# schematic.net
KiCad netlist of a schematic drawn in EAGLE
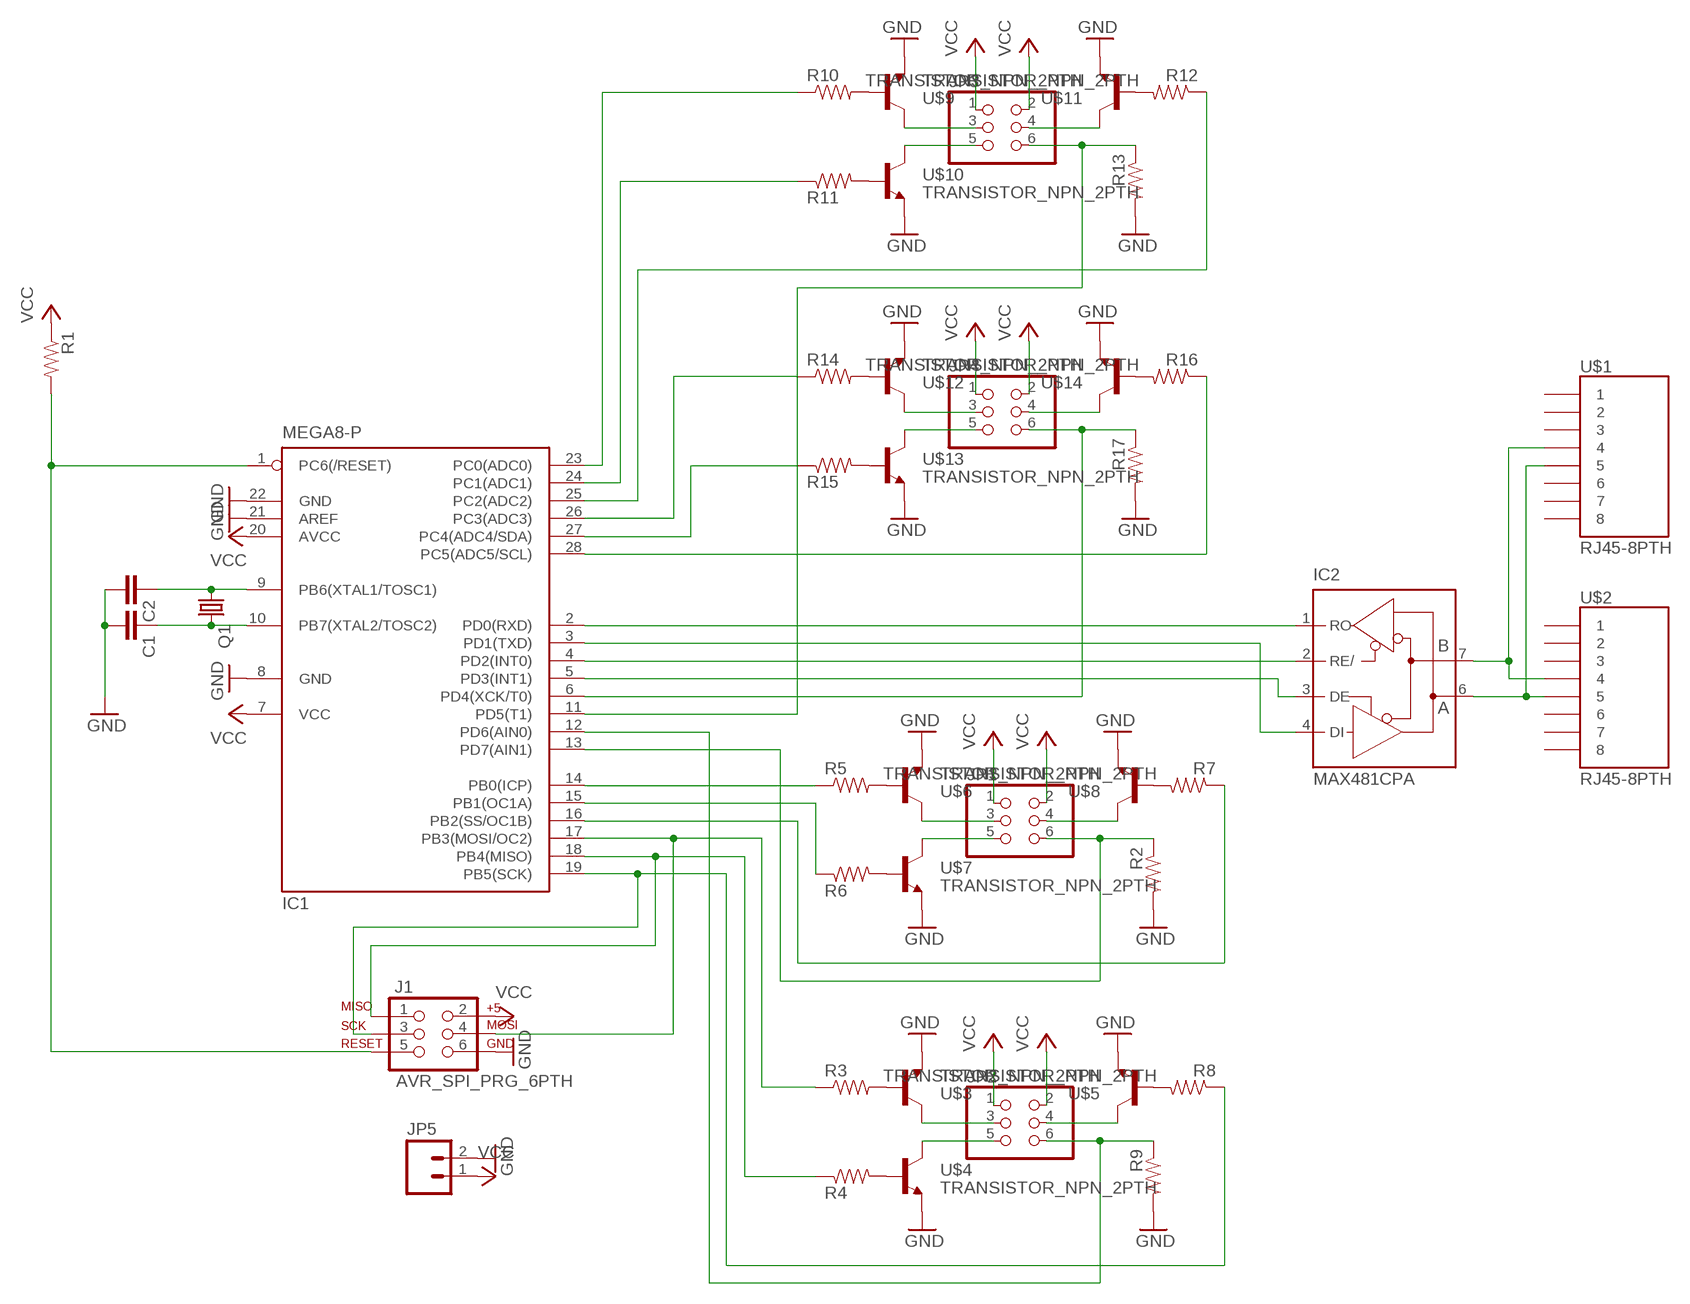
[diagram p0: schematic, sheet 1]

(export (version "E")
  (design (tool "Eeschema 10.0.6"))
  (components
    (comp (ref "C1")
      (value "CAPKIT")
      (footprint "eagle-import:CAP-PTH-SMALL-KIT")
      (libsource (lib "eagle-import") (part "CAPKIT"))
    )
    (comp (ref "C2")
      (value "CAPKIT")
      (footprint "eagle-import:CAP-PTH-SMALL-KIT")
      (libsource (lib "eagle-import") (part "CAPKIT"))
    )
    (comp (ref "IC1")
      (value "MEGA8-P")
      (footprint "eagle-import:DIL28-3")
      (libsource (lib "eagle-import") (part "MEGA8-P"))
    )
    (comp (ref "IC2")
      (value "MAX481CPA")
      (footprint "eagle-import:DIL08")
      (fields (field (name "MPN") "MAX481CPA+"))
      (libsource (lib "eagle-import") (part "MAX481CPA"))
    )
    (comp (ref "J1")
      (value "AVR_SPI_PRG_6PTH")
      (footprint "eagle-import:2X3")
      (libsource (lib "eagle-import") (part "AVR_SPI_PRG_6PTH"))
    )
    (comp (ref "JP1")
      (value "PINHD-2X3")
      (footprint "eagle-import:2X03")
      (libsource (lib "eagle-import") (part "PINHD-2X3"))
    )
    (comp (ref "JP2")
      (value "PINHD-2X3")
      (footprint "eagle-import:2X03")
      (libsource (lib "eagle-import") (part "PINHD-2X3"))
    )
    (comp (ref "JP3")
      (value "PINHD-2X3")
      (footprint "eagle-import:2X03")
      (libsource (lib "eagle-import") (part "PINHD-2X3"))
    )
    (comp (ref "JP4")
      (value "PINHD-2X3")
      (footprint "eagle-import:2X03")
      (libsource (lib "eagle-import") (part "PINHD-2X3"))
    )
    (comp (ref "JP5")
      (value "M023.5MM")
      (footprint "eagle-import:SCREWTERMINAL-3.5MM-2")
      (libsource (lib "eagle-import") (part "M023.5MM"))
    )
    (comp (ref "Q1")
      (value "CRYSTALHC49U-V")
      (footprint "eagle-import:HC49U-V")
      (libsource (lib "eagle-import") (part "CRYSTALHC49U-V"))
    )
    (comp (ref "R1")
      (value "RESISTORPTH-1/4W")
      (footprint "eagle-import:AXIAL-0.4")
      (libsource (lib "eagle-import") (part "RESISTORPTH-1/4W"))
    )
    (comp (ref "R2")
      (value "RESISTORPTH-1/4W")
      (footprint "eagle-import:AXIAL-0.4")
      (libsource (lib "eagle-import") (part "RESISTORPTH-1/4W"))
    )
    (comp (ref "R3")
      (value "RESISTORPTH-1/4W")
      (footprint "eagle-import:AXIAL-0.4")
      (libsource (lib "eagle-import") (part "RESISTORPTH-1/4W"))
    )
    (comp (ref "R4")
      (value "RESISTORPTH-1/4W")
      (footprint "eagle-import:AXIAL-0.4")
      (libsource (lib "eagle-import") (part "RESISTORPTH-1/4W"))
    )
    (comp (ref "R5")
      (value "RESISTORPTH-1/4W")
      (footprint "eagle-import:AXIAL-0.4")
      (libsource (lib "eagle-import") (part "RESISTORPTH-1/4W"))
    )
    (comp (ref "R6")
      (value "RESISTORPTH-1/4W")
      (footprint "eagle-import:AXIAL-0.4")
      (libsource (lib "eagle-import") (part "RESISTORPTH-1/4W"))
    )
    (comp (ref "R7")
      (value "RESISTORPTH-1/4W")
      (footprint "eagle-import:AXIAL-0.4")
      (libsource (lib "eagle-import") (part "RESISTORPTH-1/4W"))
    )
    (comp (ref "R8")
      (value "RESISTORPTH-1/4W")
      (footprint "eagle-import:AXIAL-0.4")
      (libsource (lib "eagle-import") (part "RESISTORPTH-1/4W"))
    )
    (comp (ref "R9")
      (value "RESISTORPTH-1/4W")
      (footprint "eagle-import:AXIAL-0.4")
      (libsource (lib "eagle-import") (part "RESISTORPTH-1/4W"))
    )
    (comp (ref "R10")
      (value "RESISTORPTH-1/4W")
      (footprint "eagle-import:AXIAL-0.4")
      (libsource (lib "eagle-import") (part "RESISTORPTH-1/4W"))
    )
    (comp (ref "R11")
      (value "RESISTORPTH-1/4W")
      (footprint "eagle-import:AXIAL-0.4")
      (libsource (lib "eagle-import") (part "RESISTORPTH-1/4W"))
    )
    (comp (ref "R12")
      (value "RESISTORPTH-1/4W")
      (footprint "eagle-import:AXIAL-0.4")
      (libsource (lib "eagle-import") (part "RESISTORPTH-1/4W"))
    )
    (comp (ref "R13")
      (value "RESISTORPTH-1/4W")
      (footprint "eagle-import:AXIAL-0.4")
      (libsource (lib "eagle-import") (part "RESISTORPTH-1/4W"))
    )
    (comp (ref "R14")
      (value "RESISTORPTH-1/4W")
      (footprint "eagle-import:AXIAL-0.4")
      (libsource (lib "eagle-import") (part "RESISTORPTH-1/4W"))
    )
    (comp (ref "R15")
      (value "RESISTORPTH-1/4W")
      (footprint "eagle-import:AXIAL-0.4")
      (libsource (lib "eagle-import") (part "RESISTORPTH-1/4W"))
    )
    (comp (ref "R16")
      (value "RESISTORPTH-1/4W")
      (footprint "eagle-import:AXIAL-0.4")
      (libsource (lib "eagle-import") (part "RESISTORPTH-1/4W"))
    )
    (comp (ref "R17")
      (value "RESISTORPTH-1/4W")
      (footprint "eagle-import:AXIAL-0.4")
      (libsource (lib "eagle-import") (part "RESISTORPTH-1/4W"))
    )
    (comp (ref "U$1")
      (value "RJ45-8PTH")
      (footprint "eagle-import:RJ45-8")
      (libsource (lib "eagle-import") (part "RJ45-8PTH"))
    )
    (comp (ref "U$2")
      (value "RJ45-8PTH")
      (footprint "eagle-import:RJ45-8")
      (libsource (lib "eagle-import") (part "RJ45-8PTH"))
    )
    (comp (ref "U$3")
      (value "TRANSISTOR_NPN_2PTH")
      (footprint "eagle-import:TO-92")
      (libsource (lib "eagle-import") (part "TRANSISTOR_NPN_2PTH"))
    )
    (comp (ref "U$4")
      (value "TRANSISTOR_NPN_2PTH")
      (footprint "eagle-import:TO-92")
      (libsource (lib "eagle-import") (part "TRANSISTOR_NPN_2PTH"))
    )
    (comp (ref "U$5")
      (value "TRANSISTOR_NPN_2PTH")
      (footprint "eagle-import:TO-92")
      (libsource (lib "eagle-import") (part "TRANSISTOR_NPN_2PTH"))
    )
    (comp (ref "U$6")
      (value "TRANSISTOR_NPN_2PTH")
      (footprint "eagle-import:TO-92")
      (libsource (lib "eagle-import") (part "TRANSISTOR_NPN_2PTH"))
    )
    (comp (ref "U$7")
      (value "TRANSISTOR_NPN_2PTH")
      (footprint "eagle-import:TO-92")
      (libsource (lib "eagle-import") (part "TRANSISTOR_NPN_2PTH"))
    )
    (comp (ref "U$8")
      (value "TRANSISTOR_NPN_2PTH")
      (footprint "eagle-import:TO-92")
      (libsource (lib "eagle-import") (part "TRANSISTOR_NPN_2PTH"))
    )
    (comp (ref "U$9")
      (value "TRANSISTOR_NPN_2PTH")
      (footprint "eagle-import:TO-92")
      (libsource (lib "eagle-import") (part "TRANSISTOR_NPN_2PTH"))
    )
    (comp (ref "U$10")
      (value "TRANSISTOR_NPN_2PTH")
      (footprint "eagle-import:TO-92")
      (libsource (lib "eagle-import") (part "TRANSISTOR_NPN_2PTH"))
    )
    (comp (ref "U$11")
      (value "TRANSISTOR_NPN_2PTH")
      (footprint "eagle-import:TO-92")
      (libsource (lib "eagle-import") (part "TRANSISTOR_NPN_2PTH"))
    )
    (comp (ref "U$12")
      (value "TRANSISTOR_NPN_2PTH")
      (footprint "eagle-import:TO-92")
      (libsource (lib "eagle-import") (part "TRANSISTOR_NPN_2PTH"))
    )
    (comp (ref "U$13")
      (value "TRANSISTOR_NPN_2PTH")
      (footprint "eagle-import:TO-92")
      (libsource (lib "eagle-import") (part "TRANSISTOR_NPN_2PTH"))
    )
    (comp (ref "U$14")
      (value "TRANSISTOR_NPN_2PTH")
      (footprint "eagle-import:TO-92")
      (libsource (lib "eagle-import") (part "TRANSISTOR_NPN_2PTH"))
    )
  )
  (nets
    (net (code "1") (name "GND") (class "Default")
      (node (ref "C1") (pin "2") (pinfunction "2_2") (pintype "passive"))
      (node (ref "C2") (pin "2") (pinfunction "2_2") (pintype "passive"))
      (node (ref "IC1") (pin "21") (pinfunction "AREF_21") (pintype "passive"))
      (node (ref "IC1") (pin "22") (pinfunction "GND_22") (pintype "power_in"))
      (node (ref "IC1") (pin "8") (pinfunction "GND_8") (pintype "power_in"))
      (node (ref "J1") (pin "6") (pinfunction "6_6") (pintype "passive"))
      (node (ref "JP5") (pin "2") (pinfunction "2_2") (pintype "passive"))
      (node (ref "R13") (pin "P$2") (pinfunction "2_P$2") (pintype "passive"))
      (node (ref "R17") (pin "P$2") (pinfunction "2_P$2") (pintype "passive"))
      (node (ref "R2") (pin "P$2") (pinfunction "2_P$2") (pintype "passive"))
      (node (ref "R9") (pin "P$2") (pinfunction "2_P$2") (pintype "passive"))
      (node (ref "U$10") (pin "3") (pinfunction "E_3") (pintype "passive"))
      (node (ref "U$11") (pin "3") (pinfunction "E_3") (pintype "passive"))
      (node (ref "U$12") (pin "3") (pinfunction "E_3") (pintype "passive"))
      (node (ref "U$13") (pin "3") (pinfunction "E_3") (pintype "passive"))
      (node (ref "U$14") (pin "3") (pinfunction "E_3") (pintype "passive"))
      (node (ref "U$3") (pin "3") (pinfunction "E_3") (pintype "passive"))
      (node (ref "U$4") (pin "3") (pinfunction "E_3") (pintype "passive"))
      (node (ref "U$5") (pin "3") (pinfunction "E_3") (pintype "passive"))
      (node (ref "U$6") (pin "3") (pinfunction "E_3") (pintype "passive"))
      (node (ref "U$7") (pin "3") (pinfunction "E_3") (pintype "passive"))
      (node (ref "U$8") (pin "3") (pinfunction "E_3") (pintype "passive"))
      (node (ref "U$9") (pin "3") (pinfunction "E_3") (pintype "passive"))
    )
    (net (code "2") (name "Net-(IC1-PB0(ICP))") (class "Default")
      (node (ref "IC1") (pin "14") (pinfunction "PB0(ICP)_14") (pintype "bidirectional"))
      (node (ref "R5") (pin "P$1") (pinfunction "1_P$1") (pintype "passive"))
    )
    (net (code "3") (name "Net-(IC1-PB1(OC1A))") (class "Default")
      (node (ref "IC1") (pin "15") (pinfunction "PB1(OC1A)_15") (pintype "bidirectional"))
      (node (ref "R6") (pin "P$1") (pinfunction "1_P$1") (pintype "passive"))
    )
    (net (code "4") (name "Net-(IC1-PB2(SS{slash}OC1B))") (class "Default")
      (node (ref "IC1") (pin "16") (pinfunction "PB2(SS/OC1B)_16") (pintype "bidirectional"))
      (node (ref "R7") (pin "P$1") (pinfunction "1_P$1") (pintype "passive"))
    )
    (net (code "5") (name "Net-(IC1-PB3(MOSI{slash}OC2))") (class "Default")
      (node (ref "IC1") (pin "17") (pinfunction "PB3(MOSI/OC2)_17") (pintype "bidirectional"))
      (node (ref "J1") (pin "4") (pinfunction "4_4") (pintype "passive"))
      (node (ref "R3") (pin "P$1") (pinfunction "1_P$1") (pintype "passive"))
    )
    (net (code "6") (name "Net-(IC1-PB4(MISO))") (class "Default")
      (node (ref "IC1") (pin "18") (pinfunction "PB4(MISO)_18") (pintype "bidirectional"))
      (node (ref "J1") (pin "1") (pinfunction "1_1") (pintype "passive"))
      (node (ref "R4") (pin "P$1") (pinfunction "1_P$1") (pintype "passive"))
    )
    (net (code "7") (name "Net-(IC1-PB5(SCK))") (class "Default")
      (node (ref "IC1") (pin "19") (pinfunction "PB5(SCK)_19") (pintype "bidirectional"))
      (node (ref "J1") (pin "3") (pinfunction "3_3") (pintype "passive"))
      (node (ref "R8") (pin "P$1") (pinfunction "1_P$1") (pintype "passive"))
    )
    (net (code "8") (name "Net-(IC1-PB6(XTAL1{slash}TOSC1))") (class "Default")
      (node (ref "C2") (pin "1") (pinfunction "1_1") (pintype "passive"))
      (node (ref "IC1") (pin "9") (pinfunction "PB6(XTAL1/TOSC1)_9") (pintype "bidirectional"))
      (node (ref "Q1") (pin "1") (pinfunction "1_1") (pintype "passive"))
    )
    (net (code "9") (name "Net-(IC1-PB7(XTAL2{slash}TOSC2))") (class "Default")
      (node (ref "C1") (pin "1") (pinfunction "1_1") (pintype "passive"))
      (node (ref "IC1") (pin "10") (pinfunction "PB7(XTAL2/TOSC2)_10") (pintype "bidirectional"))
      (node (ref "Q1") (pin "2") (pinfunction "2_2") (pintype "passive"))
    )
    (net (code "10") (name "Net-(IC1-PC0(ADC0))") (class "Default")
      (node (ref "IC1") (pin "23") (pinfunction "PC0(ADC0)_23") (pintype "bidirectional"))
      (node (ref "R10") (pin "P$1") (pinfunction "1_P$1") (pintype "passive"))
    )
    (net (code "11") (name "Net-(IC1-PC1(ADC1))") (class "Default")
      (node (ref "IC1") (pin "24") (pinfunction "PC1(ADC1)_24") (pintype "bidirectional"))
      (node (ref "R11") (pin "P$1") (pinfunction "1_P$1") (pintype "passive"))
    )
    (net (code "12") (name "Net-(IC1-PC2(ADC2))") (class "Default")
      (node (ref "IC1") (pin "25") (pinfunction "PC2(ADC2)_25") (pintype "bidirectional"))
      (node (ref "R12") (pin "P$1") (pinfunction "1_P$1") (pintype "passive"))
    )
    (net (code "13") (name "Net-(IC1-PC3(ADC3))") (class "Default")
      (node (ref "IC1") (pin "26") (pinfunction "PC3(ADC3)_26") (pintype "bidirectional"))
      (node (ref "R14") (pin "P$1") (pinfunction "1_P$1") (pintype "passive"))
    )
    (net (code "14") (name "Net-(IC1-PC4(ADC4{slash}SDA))") (class "Default")
      (node (ref "IC1") (pin "27") (pinfunction "PC4(ADC4/SDA)_27") (pintype "bidirectional"))
      (node (ref "R15") (pin "P$1") (pinfunction "1_P$1") (pintype "passive"))
    )
    (net (code "15") (name "Net-(IC1-PC5(ADC5{slash}SCL))") (class "Default")
      (node (ref "IC1") (pin "28") (pinfunction "PC5(ADC5/SCL)_28") (pintype "bidirectional"))
      (node (ref "R16") (pin "P$1") (pinfunction "1_P$1") (pintype "passive"))
    )
    (net (code "16") (name "Net-(IC1-PC6({slash}RESET))") (class "Default")
      (node (ref "IC1") (pin "1") (pinfunction "PC6(/RESET)_1") (pintype "bidirectional"))
      (node (ref "J1") (pin "5") (pinfunction "5_5") (pintype "passive"))
      (node (ref "R1") (pin "P$2") (pinfunction "2_P$2") (pintype "passive"))
    )
    (net (code "17") (name "Net-(IC1-PD0(RXD))") (class "Default")
      (node (ref "IC1") (pin "2") (pinfunction "PD0(RXD)_2") (pintype "bidirectional"))
      (node (ref "IC2") (pin "1") (pinfunction "RO_1") (pintype "output"))
    )
    (net (code "18") (name "Net-(IC1-PD1(TXD))") (class "Default")
      (node (ref "IC1") (pin "3") (pinfunction "PD1(TXD)_3") (pintype "bidirectional"))
      (node (ref "IC2") (pin "4") (pinfunction "DI_4") (pintype "input"))
    )
    (net (code "19") (name "Net-(IC1-PD2(INT0))") (class "Default")
      (node (ref "IC1") (pin "4") (pinfunction "PD2(INT0)_4") (pintype "bidirectional"))
      (node (ref "IC2") (pin "2") (pinfunction "RE/_2") (pintype "input"))
    )
    (net (code "20") (name "Net-(IC1-PD3(INT1))") (class "Default")
      (node (ref "IC1") (pin "5") (pinfunction "PD3(INT1)_5") (pintype "bidirectional"))
      (node (ref "IC2") (pin "3") (pinfunction "DE_3") (pintype "input"))
    )
    (net (code "21") (name "Net-(IC1-PD4(XCK{slash}T0))") (class "Default")
      (node (ref "IC1") (pin "6") (pinfunction "PD4(XCK/T0)_6") (pintype "bidirectional"))
      (node (ref "JP4") (pin "6") (pinfunction "6_6") (pintype "passive"))
      (node (ref "R17") (pin "P$1") (pinfunction "1_P$1") (pintype "passive"))
    )
    (net (code "22") (name "Net-(IC1-PD5(T1))") (class "Default")
      (node (ref "IC1") (pin "11") (pinfunction "PD5(T1)_11") (pintype "bidirectional"))
      (node (ref "JP3") (pin "6") (pinfunction "6_6") (pintype "passive"))
      (node (ref "R13") (pin "P$1") (pinfunction "1_P$1") (pintype "passive"))
    )
    (net (code "23") (name "Net-(IC1-PD6(AIN0))") (class "Default")
      (node (ref "IC1") (pin "12") (pinfunction "PD6(AIN0)_12") (pintype "bidirectional"))
      (node (ref "JP2") (pin "6") (pinfunction "6_6") (pintype "passive"))
      (node (ref "R9") (pin "P$1") (pinfunction "1_P$1") (pintype "passive"))
    )
    (net (code "24") (name "Net-(IC1-PD7(AIN1))") (class "Default")
      (node (ref "IC1") (pin "13") (pinfunction "PD7(AIN1)_13") (pintype "bidirectional"))
      (node (ref "JP1") (pin "6") (pinfunction "6_6") (pintype "passive"))
      (node (ref "R2") (pin "P$1") (pinfunction "1_P$1") (pintype "passive"))
    )
    (net (code "25") (name "Net-(IC2A-A)") (class "Default")
      (node (ref "IC2") (pin "6") (pinfunction "A_6") (pintype "passive"))
      (node (ref "U$1") (pin "5") (pinfunction "5_5") (pintype "bidirectional"))
      (node (ref "U$2") (pin "5") (pinfunction "5_5") (pintype "bidirectional"))
    )
    (net (code "26") (name "Net-(IC2A-B)") (class "Default")
      (node (ref "IC2") (pin "7") (pinfunction "B_7") (pintype "passive"))
      (node (ref "U$1") (pin "4") (pinfunction "4_4") (pintype "bidirectional"))
      (node (ref "U$2") (pin "4") (pinfunction "4_4") (pintype "bidirectional"))
    )
    (net (code "27") (name "Net-(R3-2)") (class "Default")
      (node (ref "R3") (pin "P$2") (pinfunction "2_P$2") (pintype "passive"))
      (node (ref "U$3") (pin "2") (pinfunction "B_2") (pintype "passive"))
    )
    (net (code "28") (name "Net-(R4-2)") (class "Default")
      (node (ref "R4") (pin "P$2") (pinfunction "2_P$2") (pintype "passive"))
      (node (ref "U$4") (pin "2") (pinfunction "B_2") (pintype "passive"))
    )
    (net (code "29") (name "Net-(R5-2)") (class "Default")
      (node (ref "R5") (pin "P$2") (pinfunction "2_P$2") (pintype "passive"))
      (node (ref "U$6") (pin "2") (pinfunction "B_2") (pintype "passive"))
    )
    (net (code "30") (name "Net-(R6-2)") (class "Default")
      (node (ref "R6") (pin "P$2") (pinfunction "2_P$2") (pintype "passive"))
      (node (ref "U$7") (pin "2") (pinfunction "B_2") (pintype "passive"))
    )
    (net (code "31") (name "Net-(R7-2)") (class "Default")
      (node (ref "R7") (pin "P$2") (pinfunction "2_P$2") (pintype "passive"))
      (node (ref "U$8") (pin "2") (pinfunction "B_2") (pintype "passive"))
    )
    (net (code "32") (name "Net-(R8-2)") (class "Default")
      (node (ref "R8") (pin "P$2") (pinfunction "2_P$2") (pintype "passive"))
      (node (ref "U$5") (pin "2") (pinfunction "B_2") (pintype "passive"))
    )
    (net (code "33") (name "Net-(R10-2)") (class "Default")
      (node (ref "R10") (pin "P$2") (pinfunction "2_P$2") (pintype "passive"))
      (node (ref "U$9") (pin "2") (pinfunction "B_2") (pintype "passive"))
    )
    (net (code "34") (name "Net-(R11-2)") (class "Default")
      (node (ref "R11") (pin "P$2") (pinfunction "2_P$2") (pintype "passive"))
      (node (ref "U$10") (pin "2") (pinfunction "B_2") (pintype "passive"))
    )
    (net (code "35") (name "Net-(R12-2)") (class "Default")
      (node (ref "R12") (pin "P$2") (pinfunction "2_P$2") (pintype "passive"))
      (node (ref "U$11") (pin "2") (pinfunction "B_2") (pintype "passive"))
    )
    (net (code "36") (name "Net-(R14-2)") (class "Default")
      (node (ref "R14") (pin "P$2") (pinfunction "2_P$2") (pintype "passive"))
      (node (ref "U$12") (pin "2") (pinfunction "B_2") (pintype "passive"))
    )
    (net (code "37") (name "Net-(R15-2)") (class "Default")
      (node (ref "R15") (pin "P$2") (pinfunction "2_P$2") (pintype "passive"))
      (node (ref "U$13") (pin "2") (pinfunction "B_2") (pintype "passive"))
    )
    (net (code "38") (name "Net-(R16-2)") (class "Default")
      (node (ref "R16") (pin "P$2") (pinfunction "2_P$2") (pintype "passive"))
      (node (ref "U$14") (pin "2") (pinfunction "B_2") (pintype "passive"))
    )
    (net (code "39") (name "Net-(U$3-C)") (class "Default")
      (node (ref "JP2") (pin "3") (pinfunction "3_3") (pintype "passive"))
      (node (ref "U$3") (pin "1") (pinfunction "C_1") (pintype "passive"))
    )
    (net (code "40") (name "Net-(U$4-C)") (class "Default")
      (node (ref "JP2") (pin "5") (pinfunction "5_5") (pintype "passive"))
      (node (ref "U$4") (pin "1") (pinfunction "C_1") (pintype "passive"))
    )
    (net (code "41") (name "Net-(U$5-C)") (class "Default")
      (node (ref "JP2") (pin "4") (pinfunction "4_4") (pintype "passive"))
      (node (ref "U$5") (pin "1") (pinfunction "C_1") (pintype "passive"))
    )
    (net (code "42") (name "Net-(U$6-C)") (class "Default")
      (node (ref "JP1") (pin "3") (pinfunction "3_3") (pintype "passive"))
      (node (ref "U$6") (pin "1") (pinfunction "C_1") (pintype "passive"))
    )
    (net (code "43") (name "Net-(U$7-C)") (class "Default")
      (node (ref "JP1") (pin "5") (pinfunction "5_5") (pintype "passive"))
      (node (ref "U$7") (pin "1") (pinfunction "C_1") (pintype "passive"))
    )
    (net (code "44") (name "Net-(U$8-C)") (class "Default")
      (node (ref "JP1") (pin "4") (pinfunction "4_4") (pintype "passive"))
      (node (ref "U$8") (pin "1") (pinfunction "C_1") (pintype "passive"))
    )
    (net (code "45") (name "Net-(U$9-C)") (class "Default")
      (node (ref "JP3") (pin "3") (pinfunction "3_3") (pintype "passive"))
      (node (ref "U$9") (pin "1") (pinfunction "C_1") (pintype "passive"))
    )
    (net (code "46") (name "Net-(U$10-C)") (class "Default")
      (node (ref "JP3") (pin "5") (pinfunction "5_5") (pintype "passive"))
      (node (ref "U$10") (pin "1") (pinfunction "C_1") (pintype "passive"))
    )
    (net (code "47") (name "Net-(U$11-C)") (class "Default")
      (node (ref "JP3") (pin "4") (pinfunction "4_4") (pintype "passive"))
      (node (ref "U$11") (pin "1") (pinfunction "C_1") (pintype "passive"))
    )
    (net (code "48") (name "Net-(U$12-C)") (class "Default")
      (node (ref "JP4") (pin "3") (pinfunction "3_3") (pintype "passive"))
      (node (ref "U$12") (pin "1") (pinfunction "C_1") (pintype "passive"))
    )
    (net (code "49") (name "Net-(U$13-C)") (class "Default")
      (node (ref "JP4") (pin "5") (pinfunction "5_5") (pintype "passive"))
      (node (ref "U$13") (pin "1") (pinfunction "C_1") (pintype "passive"))
    )
    (net (code "50") (name "Net-(U$14-C)") (class "Default")
      (node (ref "JP4") (pin "4") (pinfunction "4_4") (pintype "passive"))
      (node (ref "U$14") (pin "1") (pinfunction "C_1") (pintype "passive"))
    )
    (net (code "51") (name "VCC") (class "Default")
      (node (ref "IC1") (pin "20") (pinfunction "AVCC_20") (pintype "power_in"))
      (node (ref "IC1") (pin "7") (pinfunction "VCC_7") (pintype "power_in"))
      (node (ref "J1") (pin "2") (pinfunction "2_2") (pintype "passive"))
      (node (ref "JP1") (pin "1") (pinfunction "1_1") (pintype "passive"))
      (node (ref "JP1") (pin "2") (pinfunction "2_2") (pintype "passive"))
      (node (ref "JP2") (pin "1") (pinfunction "1_1") (pintype "passive"))
      (node (ref "JP2") (pin "2") (pinfunction "2_2") (pintype "passive"))
      (node (ref "JP3") (pin "1") (pinfunction "1_1") (pintype "passive"))
      (node (ref "JP3") (pin "2") (pinfunction "2_2") (pintype "passive"))
      (node (ref "JP4") (pin "1") (pinfunction "1_1") (pintype "passive"))
      (node (ref "JP4") (pin "2") (pinfunction "2_2") (pintype "passive"))
      (node (ref "JP5") (pin "1") (pinfunction "1_1") (pintype "passive"))
      (node (ref "R1") (pin "P$1") (pinfunction "1_P$1") (pintype "passive"))
    )
    (net (code "52") (name "unconnected-(U$1-Pad1)") (class "Default")
      (node (ref "U$1") (pin "1") (pinfunction "1_1") (pintype "bidirectional"))
    )
    (net (code "53") (name "unconnected-(U$1-Pad2)") (class "Default")
      (node (ref "U$1") (pin "2") (pinfunction "2_2") (pintype "bidirectional"))
    )
    (net (code "54") (name "unconnected-(U$1-Pad3)") (class "Default")
      (node (ref "U$1") (pin "3") (pinfunction "3_3") (pintype "bidirectional"))
    )
    (net (code "55") (name "unconnected-(U$1-Pad6)") (class "Default")
      (node (ref "U$1") (pin "6") (pinfunction "6_6") (pintype "bidirectional"))
    )
    (net (code "56") (name "unconnected-(U$1-Pad7)") (class "Default")
      (node (ref "U$1") (pin "7") (pinfunction "7_7") (pintype "bidirectional"))
    )
    (net (code "57") (name "unconnected-(U$1-Pad8)") (class "Default")
      (node (ref "U$1") (pin "8") (pinfunction "8_8") (pintype "bidirectional"))
    )
    (net (code "58") (name "unconnected-(U$2-Pad1)") (class "Default")
      (node (ref "U$2") (pin "1") (pinfunction "1_1") (pintype "bidirectional"))
    )
    (net (code "59") (name "unconnected-(U$2-Pad2)") (class "Default")
      (node (ref "U$2") (pin "2") (pinfunction "2_2") (pintype "bidirectional"))
    )
    (net (code "60") (name "unconnected-(U$2-Pad3)") (class "Default")
      (node (ref "U$2") (pin "3") (pinfunction "3_3") (pintype "bidirectional"))
    )
    (net (code "61") (name "unconnected-(U$2-Pad6)") (class "Default")
      (node (ref "U$2") (pin "6") (pinfunction "6_6") (pintype "bidirectional"))
    )
    (net (code "62") (name "unconnected-(U$2-Pad7)") (class "Default")
      (node (ref "U$2") (pin "7") (pinfunction "7_7") (pintype "bidirectional"))
    )
    (net (code "63") (name "unconnected-(U$2-Pad8)") (class "Default")
      (node (ref "U$2") (pin "8") (pinfunction "8_8") (pintype "bidirectional"))
    )
  )
)
